# EPS_DCDC_RLCLs.net
KiCad netlist of a schematic drawn in Altium Designer
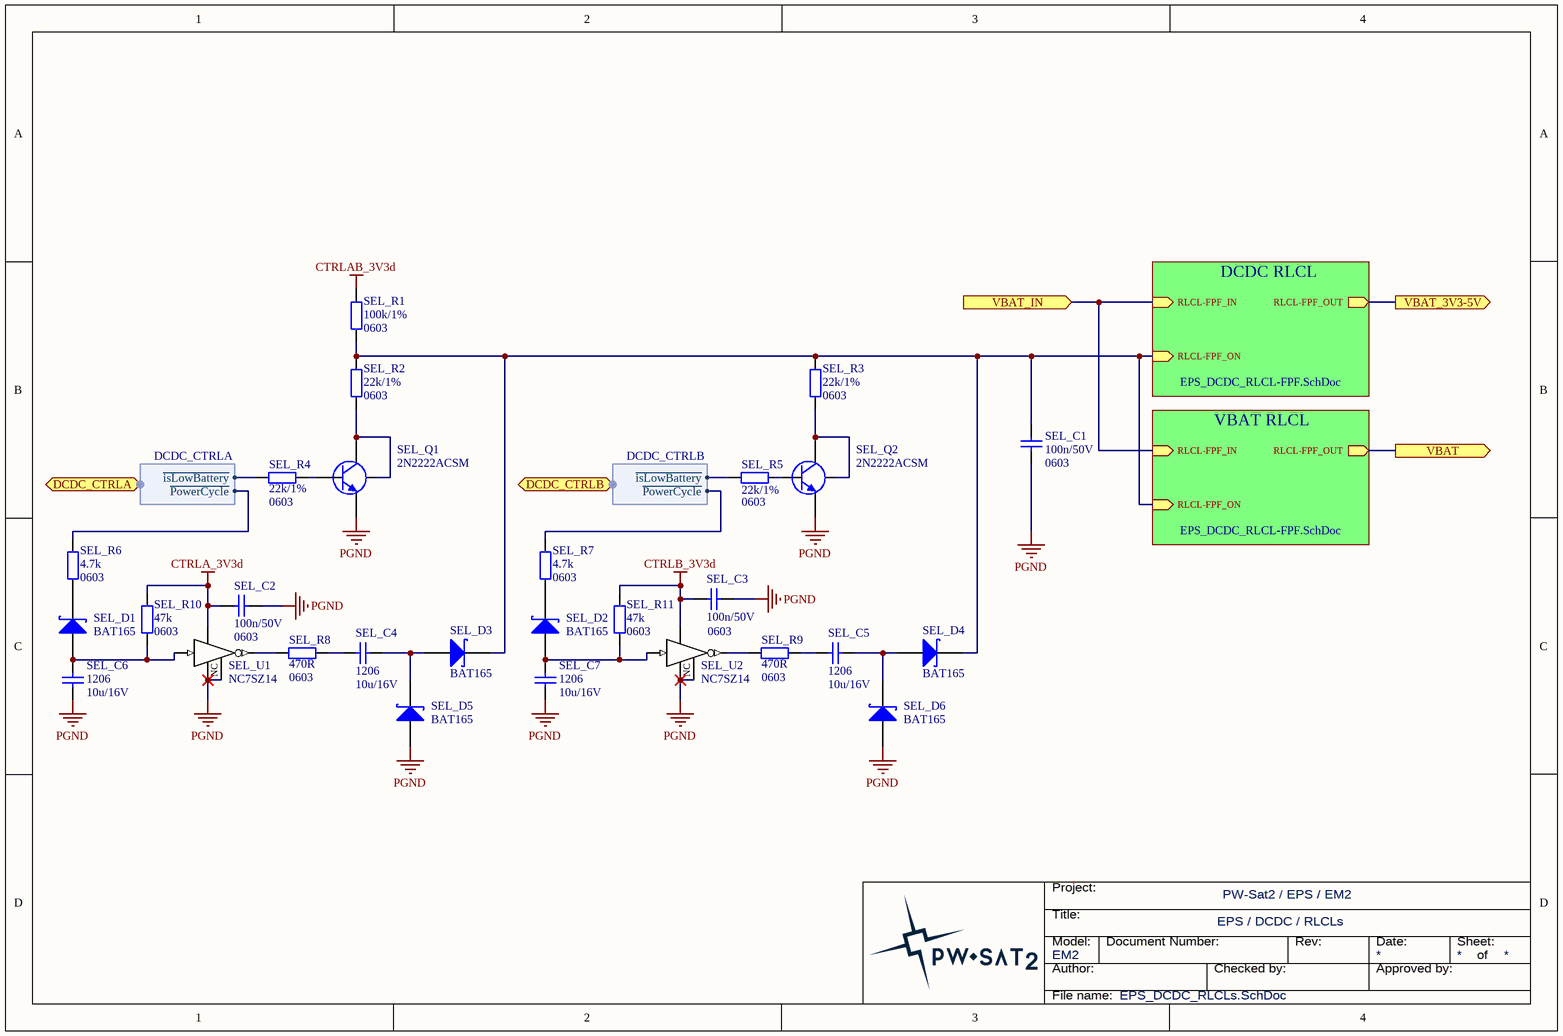
[diagram p0: EPS_DCDC_RLCLs.SchDoc]

(export (version "E")
  (design (tool "Eeschema 10.0.6"))
  (components
    (comp (ref "SEL_C1")
      (value "100n/50V")
      (footprint "SMD_Capacitor_0603")
      (description "Cap")
      (fields (field (name "PACKAGE") "0603"))
      (libsource (lib "capacitors") (part "Cap"))
    )
    (comp (ref "SEL_C2")
      (value "100n/50V")
      (footprint "SMD_Capacitor_0603")
      (description "Ceramic Cap Kemet COTS 100n/50V X7R 0603")
      (fields
        (field (name "MANUFACTURER") "Kemet")
        (field (name "MANUFACTURERPARTNUMBER") "C0603T104K5RALTU")
        (field (name "PACKAGE") "0603")
      )
      (libsource (lib "capacitors") (part "Cer_C0603T104K5RALTU"))
    )
    (comp (ref "SEL_C3")
      (value "100n/50V")
      (footprint "SMD_Capacitor_0603")
      (description "Ceramic Cap Kemet COTS 100n/50V X7R 0603")
      (fields
        (field (name "MANUFACTURER") "Kemet")
        (field (name "MANUFACTURERPARTNUMBER") "C0603T104K5RALTU")
        (field (name "PACKAGE") "0603")
      )
      (libsource (lib "capacitors") (part "Cer_C0603T104K5RALTU"))
    )
    (comp (ref "SEL_C4")
      (value "10u/16V")
      (footprint "SMD_Capacitor_1206")
      (description "Ceramic Cap Kemet COTS 10u/16V X7R 1206")
      (fields
        (field (name "MANUFACTURERPARTNUMBER") "C1206T106K4RACTU")
        (field (name "MANUFACTURER") "Kemet")
        (field (name "PACKGE") "1206")
      )
      (libsource (lib "capacitors") (part "Cer_C1206T106K4RACTU"))
    )
    (comp (ref "SEL_C5")
      (value "10u/16V")
      (footprint "SMD_Capacitor_1206")
      (description "Ceramic Cap Kemet COTS 10u/16V X7R 1206")
      (fields
        (field (name "MANUFACTURERPARTNUMBER") "C1206T106K4RACTU")
        (field (name "MANUFACTURER") "Kemet")
        (field (name "PACKGE") "1206")
      )
      (libsource (lib "capacitors") (part "Cer_C1206T106K4RACTU"))
    )
    (comp (ref "SEL_C6")
      (value "10u/16V")
      (footprint "SMD_Capacitor_1206")
      (description "Ceramic Cap Kemet COTS 10u/16V X7R 1206")
      (fields
        (field (name "MANUFACTURERPARTNUMBER") "C1206T106K4RACTU")
        (field (name "MANUFACTURER") "Kemet")
        (field (name "PACKGE") "1206")
      )
      (libsource (lib "capacitors") (part "Cer_C1206T106K4RACTU"))
    )
    (comp (ref "SEL_C7")
      (value "10u/16V")
      (footprint "SMD_Capacitor_1206")
      (description "Ceramic Cap Kemet COTS 10u/16V X7R 1206")
      (fields
        (field (name "MANUFACTURERPARTNUMBER") "C1206T106K4RACTU")
        (field (name "MANUFACTURER") "Kemet")
        (field (name "PACKGE") "1206")
      )
      (libsource (lib "capacitors") (part "Cer_C1206T106K4RACTU"))
    )
    (comp (ref "SEL_D1")
      (value "BAT165")
      (footprint "SOD323")
      (description "Madium Power AF Schottky 750mA 40V Diode")
      (fields (field (name "MANUFACTURER") "Infineon"))
      (libsource (lib "diodes") (part "BAT165"))
    )
    (comp (ref "SEL_D2")
      (value "BAT165")
      (footprint "SOD323")
      (description "Madium Power AF Schottky 750mA 40V Diode")
      (fields (field (name "MANUFACTURER") "Infineon"))
      (libsource (lib "diodes") (part "BAT165"))
    )
    (comp (ref "SEL_D3")
      (value "BAT165")
      (footprint "SOD323")
      (description "Madium Power AF Schottky 750mA 40V Diode")
      (fields (field (name "MANUFACTURER") "Infineon"))
      (libsource (lib "diodes") (part "BAT165"))
    )
    (comp (ref "SEL_D4")
      (value "BAT165")
      (footprint "SOD323")
      (description "Madium Power AF Schottky 750mA 40V Diode")
      (fields (field (name "MANUFACTURER") "Infineon"))
      (libsource (lib "diodes") (part "BAT165"))
    )
    (comp (ref "SEL_D5")
      (value "BAT165")
      (footprint "SOD323")
      (description "Madium Power AF Schottky 750mA 40V Diode")
      (fields (field (name "MANUFACTURER") "Infineon"))
      (libsource (lib "diodes") (part "BAT165"))
    )
    (comp (ref "SEL_D6")
      (value "BAT165")
      (footprint "SOD323")
      (description "Madium Power AF Schottky 750mA 40V Diode")
      (fields (field (name "MANUFACTURER") "Infineon"))
      (libsource (lib "diodes") (part "BAT165"))
    )
    (comp (ref "SEL_Q1")
      (value "2N2222ACSM")
      (footprint "LCC1-4_BEC")
      (description "Silicon Planar Epitaxial NPN Transistor.")
      (fields (field (name "MANUFACTURER") "Semelab-TT"))
      (libsource (lib "transistors") (part "2N2222ACSM"))
    )
    (comp (ref "SEL_Q2")
      (value "2N2222ACSM")
      (footprint "LCC1-4_BEC")
      (description "Silicon Planar Epitaxial NPN Transistor.")
      (fields (field (name "MANUFACTURER") "Semelab-TT"))
      (libsource (lib "transistors") (part "2N2222ACSM"))
    )
    (comp (ref "SEL_R1")
      (value "100k/1%")
      (footprint "SMD_Resistor_0603")
      (fields (field (name "PACKAGE") "0603"))
      (libsource (lib "") (part "Res_1"))
    )
    (comp (ref "SEL_R2")
      (value "22k/1%")
      (footprint "SMD_Resistor_0603")
      (fields (field (name "PACKAGE") "0603"))
      (libsource (lib "") (part "Res_1"))
    )
    (comp (ref "SEL_R3")
      (value "22k/1%")
      (footprint "SMD_Resistor_0603")
      (fields (field (name "PACKAGE") "0603"))
      (libsource (lib "") (part "Res_1"))
    )
    (comp (ref "SEL_R4")
      (value "22k/1%")
      (footprint "SMD_Resistor_0603")
      (fields (field (name "PACKAGE") "0603"))
      (libsource (lib "resistors") (part "Res"))
    )
    (comp (ref "SEL_R5")
      (value "22k/1%")
      (footprint "SMD_Resistor_0603")
      (fields (field (name "PACKAGE") "0603"))
      (libsource (lib "resistors") (part "Res"))
    )
    (comp (ref "SEL_R6")
      (value "4.7k")
      (footprint "SMD_Resistor_0603")
      (fields (field (name "PACKAGE") "0603"))
      (libsource (lib "") (part "Res_1"))
    )
    (comp (ref "SEL_R7")
      (value "4.7k")
      (footprint "SMD_Resistor_0603")
      (fields (field (name "PACKAGE") "0603"))
      (libsource (lib "") (part "Res_1"))
    )
    (comp (ref "SEL_R8")
      (value "470R")
      (footprint "SMD_Resistor_0603")
      (fields (field (name "PACKAGE") "0603"))
      (libsource (lib "resistors") (part "Res"))
    )
    (comp (ref "SEL_R9")
      (value "470R")
      (footprint "SMD_Resistor_0603")
      (fields (field (name "PACKAGE") "0603"))
      (libsource (lib "resistors") (part "Res"))
    )
    (comp (ref "SEL_R10")
      (value "47k")
      (footprint "SMD_Resistor_0603")
      (fields (field (name "PACKAGE") "0603"))
      (libsource (lib "") (part "Res_1"))
    )
    (comp (ref "SEL_R11")
      (value "47k")
      (footprint "SMD_Resistor_0603")
      (fields (field (name "PACKAGE") "0603"))
      (libsource (lib "") (part "Res_1"))
    )
    (comp (ref "SEL_U1")
      (value "NC7SZ14")
      (footprint "SOT23-5")
      (description "TinyLogic UHS TinyLogic UHS Two-Input NAND Gate.")
      (fields (field (name "MANUFACTURER") "Fairchild Semiconductor"))
      (libsource (lib "microcircuits") (part "NC7SZ14"))
    )
    (comp (ref "SEL_U2")
      (value "NC7SZ14")
      (footprint "SOT23-5")
      (description "TinyLogic UHS TinyLogic UHS Two-Input NAND Gate.")
      (fields (field (name "MANUFACTURER") "Fairchild Semiconductor"))
      (libsource (lib "microcircuits") (part "NC7SZ14"))
    )
  )
  (nets
    (net (code "3") (name "/RLCL-FPF_ON") (class "Default")
      (node (ref "SEL_C1") (pin "1") (pinfunction "1_1") (pintype "passive"))
      (node (ref "SEL_D3") (pin "K") (pinfunction "K_K") (pintype "passive"))
      (node (ref "SEL_D4") (pin "K") (pinfunction "K_K") (pintype "passive"))
      (node (ref "SEL_R1") (pin "1") (pinfunction "1_1") (pintype "passive"))
      (node (ref "SEL_R2") (pin "2") (pinfunction "2_2") (pintype "passive"))
      (node (ref "SEL_R3") (pin "2") (pinfunction "2_2") (pintype "passive"))
    )
    (net (code "9") (name "CTRLAB_3V3d") (class "Default")
      (node (ref "SEL_R1") (pin "2") (pinfunction "2_2") (pintype "passive"))
    )
    (net (code "10") (name "CTRLA_3V3d") (class "Default")
      (node (ref "SEL_C2") (pin "1") (pinfunction "1_1") (pintype "passive"))
      (node (ref "SEL_R10") (pin "2") (pinfunction "2_2") (pintype "passive"))
      (node (ref "SEL_U1") (pin "5") (pinfunction "Vcc_5") (pintype "power_in"))
    )
    (net (code "11") (name "CTRLB_3V3d") (class "Default")
      (node (ref "SEL_C3") (pin "1") (pinfunction "1_1") (pintype "passive"))
      (node (ref "SEL_R11") (pin "2") (pinfunction "2_2") (pintype "passive"))
      (node (ref "SEL_U2") (pin "5") (pinfunction "Vcc_5") (pintype "power_in"))
    )
    (net (code "12") (name "Net-(SEL_C4-Pad1)") (class "Default")
      (node (ref "SEL_C4") (pin "1") (pinfunction "1_1") (pintype "passive"))
      (node (ref "SEL_R8") (pin "2") (pinfunction "2_2") (pintype "passive"))
    )
    (net (code "13") (name "Net-(SEL_C4-Pad2)") (class "Default")
      (node (ref "SEL_C4") (pin "2") (pinfunction "2_2") (pintype "passive"))
      (node (ref "SEL_D3") (pin "A") (pinfunction "A_A") (pintype "passive"))
      (node (ref "SEL_D5") (pin "K") (pinfunction "K_K") (pintype "passive"))
    )
    (net (code "14") (name "Net-(SEL_C5-Pad1)") (class "Default")
      (node (ref "SEL_C5") (pin "1") (pinfunction "1_1") (pintype "passive"))
      (node (ref "SEL_R9") (pin "2") (pinfunction "2_2") (pintype "passive"))
    )
    (net (code "15") (name "Net-(SEL_C5-Pad2)") (class "Default")
      (node (ref "SEL_C5") (pin "2") (pinfunction "2_2") (pintype "passive"))
      (node (ref "SEL_D4") (pin "A") (pinfunction "A_A") (pintype "passive"))
      (node (ref "SEL_D6") (pin "K") (pinfunction "K_K") (pintype "passive"))
    )
    (net (code "16") (name "Net-(SEL_D1-PadK)") (class "Default")
      (node (ref "SEL_D1") (pin "K") (pinfunction "K_K") (pintype "passive"))
      (node (ref "SEL_R6") (pin "1") (pinfunction "1_1") (pintype "passive"))
    )
    (net (code "17") (name "Net-(SEL_D2-PadK)") (class "Default")
      (node (ref "SEL_D2") (pin "K") (pinfunction "K_K") (pintype "passive"))
      (node (ref "SEL_R7") (pin "1") (pinfunction "1_1") (pintype "passive"))
    )
    (net (code "18") (name "Net-(SEL_Q1-PadB)") (class "Default")
      (node (ref "SEL_Q1") (pin "B") (pinfunction "B_B") (pintype "passive"))
      (node (ref "SEL_R4") (pin "2") (pinfunction "2_2") (pintype "passive"))
    )
    (net (code "19") (name "Net-(SEL_Q1-PadC)") (class "Default")
      (node (ref "SEL_Q1") (pin "C") (pinfunction "C_C") (pintype "passive"))
      (node (ref "SEL_Q1") (pin "Shield") (pinfunction "Shield_Shield") (pintype "passive"))
      (node (ref "SEL_R2") (pin "1") (pinfunction "1_1") (pintype "passive"))
    )
    (net (code "20") (name "Net-(SEL_Q2-PadB)") (class "Default")
      (node (ref "SEL_Q2") (pin "B") (pinfunction "B_B") (pintype "passive"))
      (node (ref "SEL_R5") (pin "2") (pinfunction "2_2") (pintype "passive"))
    )
    (net (code "21") (name "Net-(SEL_Q2-PadC)") (class "Default")
      (node (ref "SEL_Q2") (pin "C") (pinfunction "C_C") (pintype "passive"))
      (node (ref "SEL_Q2") (pin "Shield") (pinfunction "Shield_Shield") (pintype "passive"))
      (node (ref "SEL_R3") (pin "1") (pinfunction "1_1") (pintype "passive"))
    )
    (net (code "22") (name "Net-(SEL_U1-A)") (class "Default")
      (node (ref "SEL_C6") (pin "2") (pinfunction "2_2") (pintype "passive"))
      (node (ref "SEL_D1") (pin "A") (pinfunction "A_A") (pintype "passive"))
      (node (ref "SEL_R10") (pin "1") (pinfunction "1_1") (pintype "passive"))
      (node (ref "SEL_U1") (pin "2") (pinfunction "A_2") (pintype "input"))
    )
    (net (code "23") (name "Net-(SEL_U1-Y)") (class "Default")
      (node (ref "SEL_R8") (pin "1") (pinfunction "1_1") (pintype "passive"))
      (node (ref "SEL_U1") (pin "4") (pinfunction "Y_4") (pintype "output"))
    )
    (net (code "24") (name "Net-(SEL_U2-A)") (class "Default")
      (node (ref "SEL_C7") (pin "2") (pinfunction "2_2") (pintype "passive"))
      (node (ref "SEL_D2") (pin "A") (pinfunction "A_A") (pintype "passive"))
      (node (ref "SEL_R11") (pin "1") (pinfunction "1_1") (pintype "passive"))
      (node (ref "SEL_U2") (pin "2") (pinfunction "A_2") (pintype "input"))
    )
    (net (code "25") (name "Net-(SEL_U2-Y)") (class "Default")
      (node (ref "SEL_R9") (pin "1") (pinfunction "1_1") (pintype "passive"))
      (node (ref "SEL_U2") (pin "4") (pinfunction "Y_4") (pintype "output"))
    )
    (net (code "26") (name "PGND") (class "Default")
      (node (ref "SEL_C1") (pin "2") (pinfunction "2_2") (pintype "passive"))
      (node (ref "SEL_C2") (pin "2") (pinfunction "2_2") (pintype "passive"))
      (node (ref "SEL_C3") (pin "2") (pinfunction "2_2") (pintype "passive"))
      (node (ref "SEL_C6") (pin "1") (pinfunction "1_1") (pintype "passive"))
      (node (ref "SEL_C7") (pin "1") (pinfunction "1_1") (pintype "passive"))
      (node (ref "SEL_D5") (pin "A") (pinfunction "A_A") (pintype "passive"))
      (node (ref "SEL_D6") (pin "A") (pinfunction "A_A") (pintype "passive"))
      (node (ref "SEL_Q1") (pin "E") (pinfunction "E_E") (pintype "passive"))
      (node (ref "SEL_Q2") (pin "E") (pinfunction "E_E") (pintype "passive"))
      (node (ref "SEL_U1") (pin "1") (pinfunction "NC_1") (pintype "tri_state"))
      (node (ref "SEL_U1") (pin "3") (pinfunction "GND_3") (pintype "power_in"))
      (node (ref "SEL_U2") (pin "1") (pinfunction "NC_1") (pintype "tri_state"))
      (node (ref "SEL_U2") (pin "3") (pinfunction "GND_3") (pintype "power_in"))
    )
    (net (code "27") (name "unconnected-(SEL_R4-Pad1)") (class "Default")
      (node (ref "SEL_R4") (pin "1") (pinfunction "1_1") (pintype "passive"))
    )
    (net (code "28") (name "unconnected-(SEL_R5-Pad1)") (class "Default")
      (node (ref "SEL_R5") (pin "1") (pinfunction "1_1") (pintype "passive"))
    )
    (net (code "29") (name "unconnected-(SEL_R6-Pad2)") (class "Default")
      (node (ref "SEL_R6") (pin "2") (pinfunction "2_2") (pintype "passive"))
    )
    (net (code "30") (name "unconnected-(SEL_R7-Pad2)") (class "Default")
      (node (ref "SEL_R7") (pin "2") (pinfunction "2_2") (pintype "passive"))
    )
  )
)
